# 6coils.net
KiCad netlist of a schematic drawn in EasyEDA
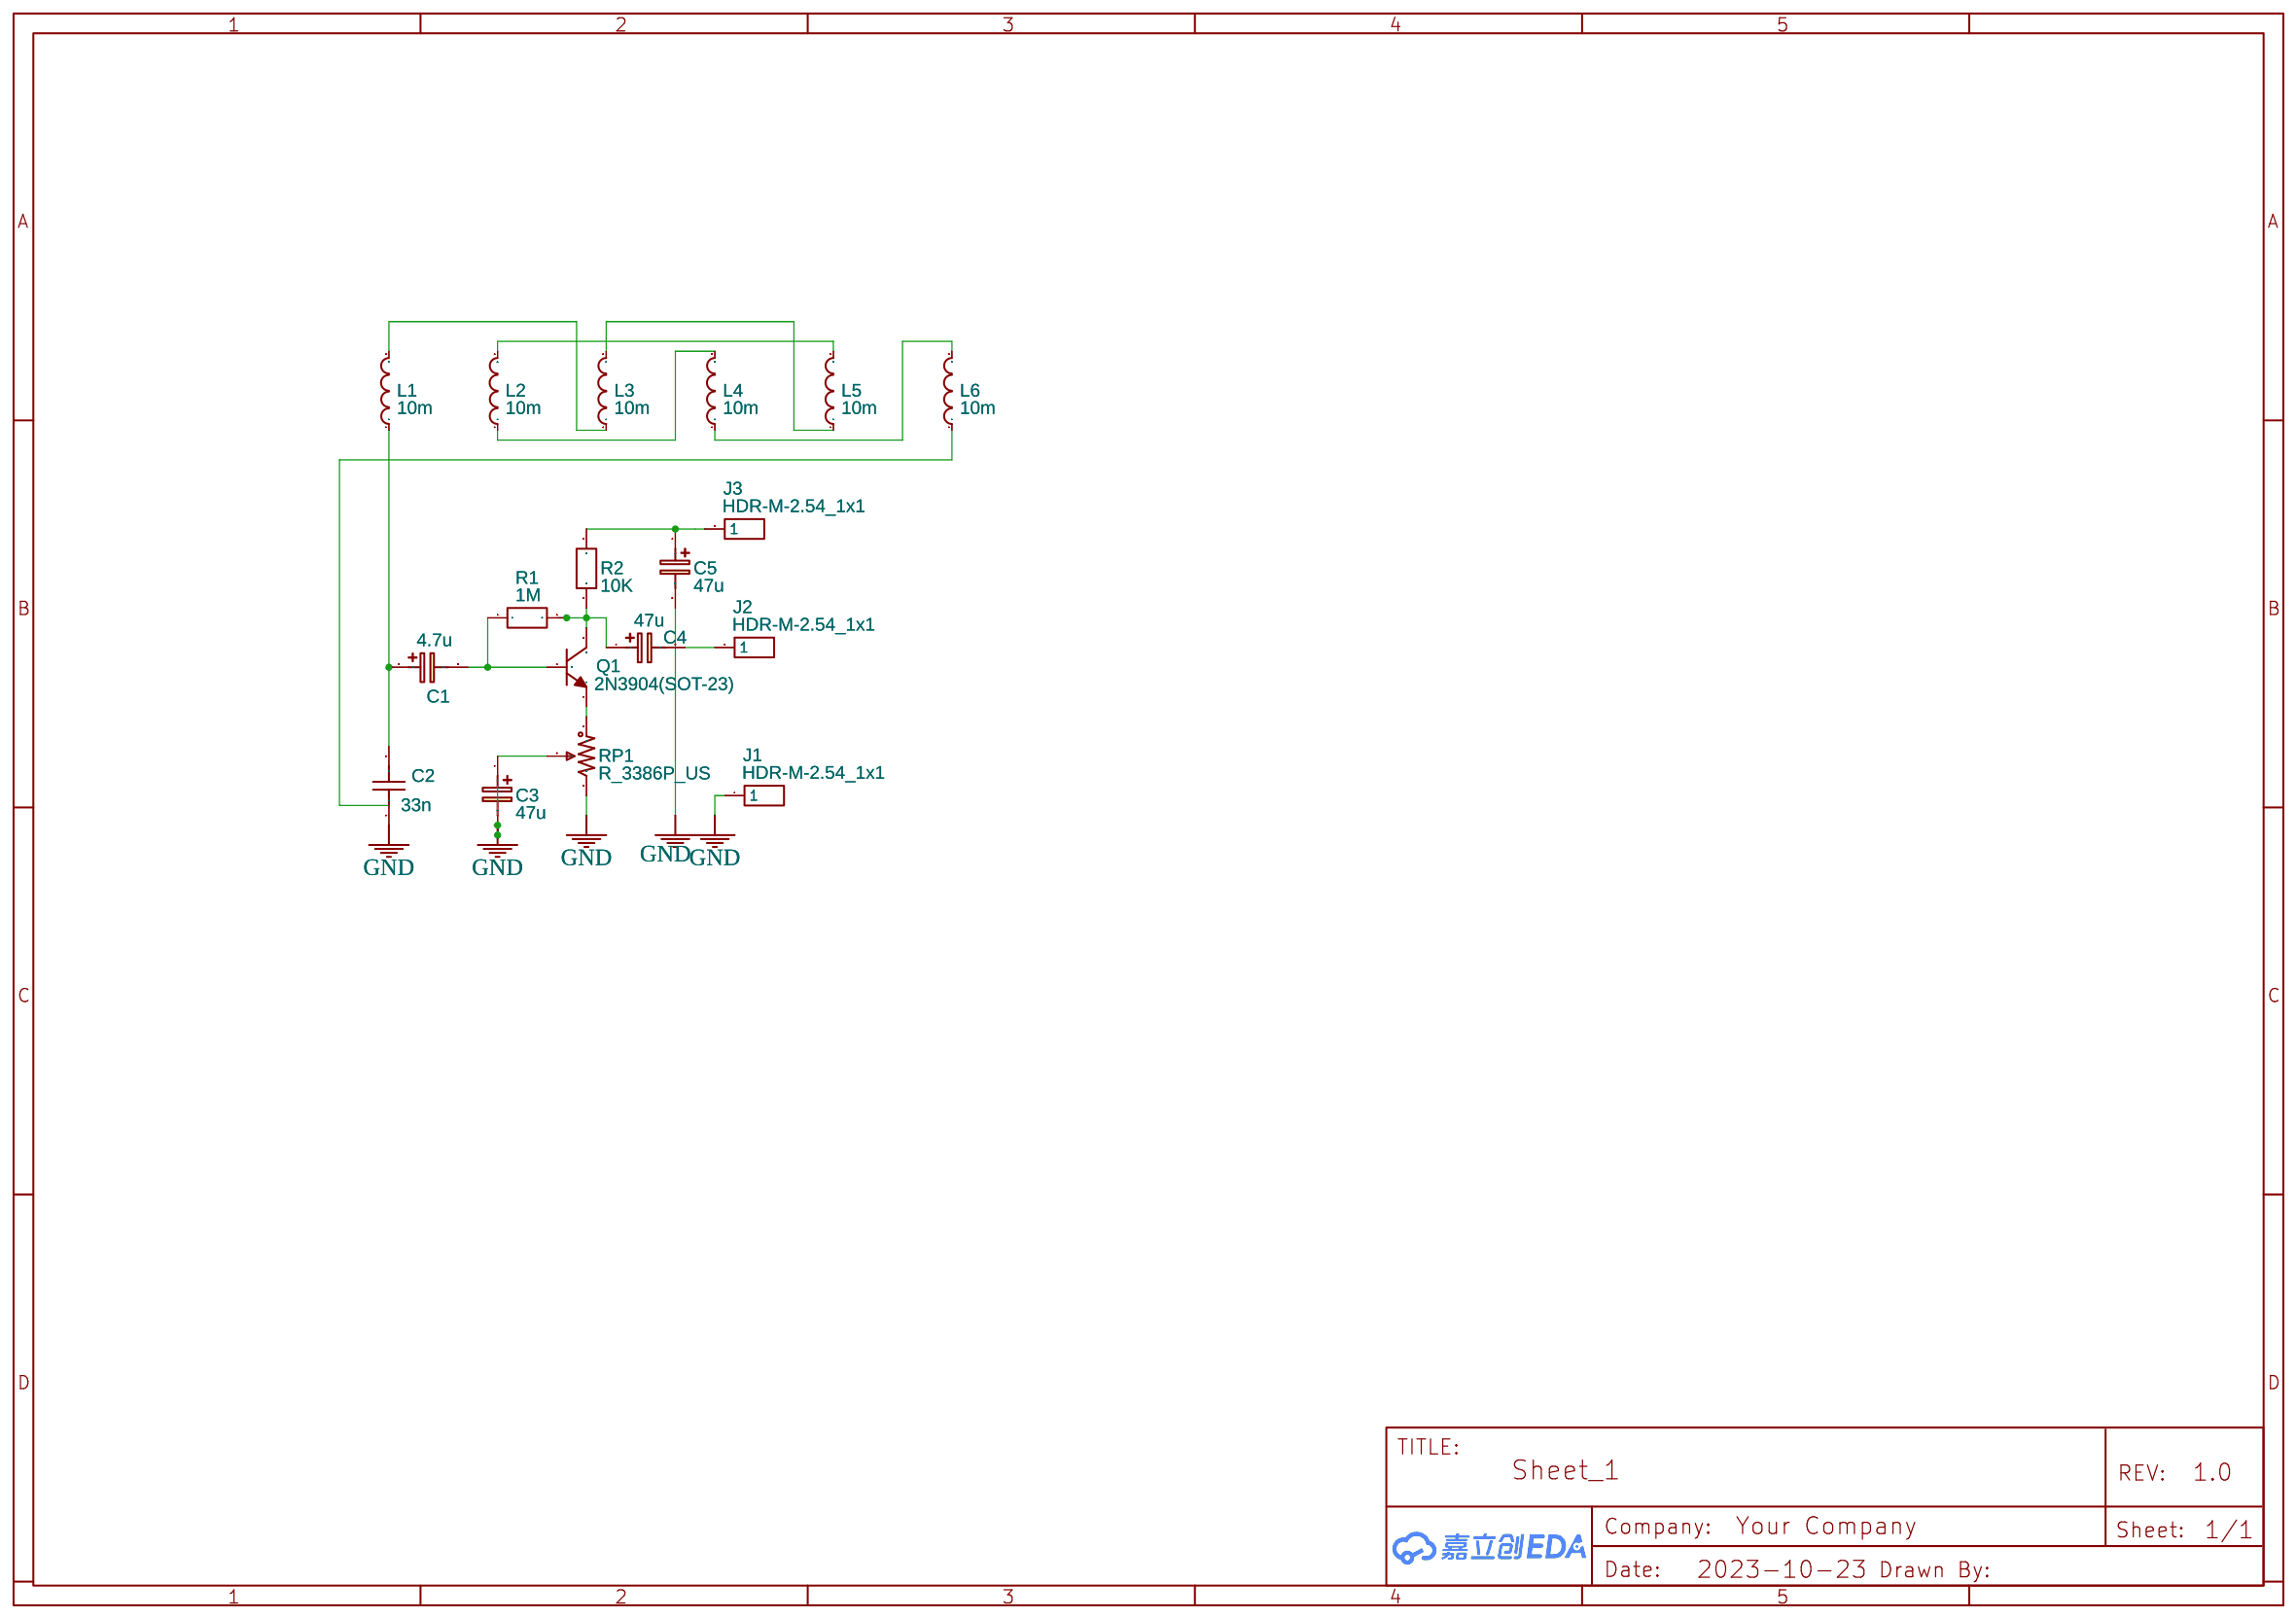
[diagram p0: schematic sheet]

(export (version "E")
  (design (tool "Eeschema 10.0.6"))
  (components
    (comp (ref "C1") (value "4.7u") (libsource (lib "") (part "C_Tan_SMD_A_EU_2")))
    (comp (ref "C2") (value "33n") (libsource (lib "") (part "C_0603_US")))
    (comp (ref "C3") (value "47u") (libsource (lib "") (part "C_Tan_SMD_A_EU")))
    (comp (ref "C4") (value "47u") (libsource (lib "") (part "C_Tan_SMD_A_EU_3")))
    (comp (ref "C5") (value "47u") (libsource (lib "") (part "C_Tan_SMD_A_EU_1")))
    (comp (ref "J1")
      (value "HDR-M-2.54_1x1")
      (fields (field (name "BOM_Supplier Part") "C81276"))
      (libsource (lib "") (part "HDR-M-2.54_1x1"))
    )
    (comp (ref "J2")
      (value "HDR-M-2.54_1x1")
      (fields (field (name "BOM_Supplier Part") "C81276"))
      (libsource (lib "") (part "HDR-M-2.54_1x1"))
    )
    (comp (ref "J3")
      (value "HDR-M-2.54_1x1")
      (fields (field (name "BOM_Supplier Part") "C81276"))
      (libsource (lib "") (part "HDR-M-2.54_1x1"))
    )
    (comp (ref "L1") (value "10m") (libsource (lib "") (part "L0603_US")))
    (comp (ref "L2") (value "10m") (libsource (lib "") (part "L0603_US")))
    (comp (ref "L3") (value "10m") (libsource (lib "") (part "L0603_US")))
    (comp (ref "L4") (value "10m") (libsource (lib "") (part "L0603_US")))
    (comp (ref "L5") (value "10m") (libsource (lib "") (part "L0603_US")))
    (comp (ref "L6") (value "10m") (libsource (lib "") (part "L0603_US")))
    (comp (ref "Q1")
      (value "2N3904(SOT-23)")
      (fields
        (field (name "BOM_Manufacturer Part") "2n3904S-RTK/PS")
        (field (name "BOM_Supplier Part") "C18536")
      )
      (libsource (lib "") (part "2N3904(SOT-23)"))
    )
    (comp (ref "R1") (value "1M") (libsource (lib "") (part "R_0603_EU_1")))
    (comp (ref "R2") (value "10K") (libsource (lib "") (part "R_0603_EU")))
    (comp (ref "RP1") (value "R_3386P_US") (libsource (lib "") (part "R_3386P_US")))
  )
  (nets
    (net (code "1") (name "GND") (class "Default")
      (node (ref "C2") (pin "1") (pinfunction "1_1") (pintype "unspecified"))
      (node (ref "C3") (pin "2") (pinfunction "2_2") (pintype "unspecified"))
      (node (ref "C5") (pin "2") (pinfunction "2_2") (pintype "unspecified"))
      (node (ref "J1") (pin "1") (pinfunction "1_1") (pintype "input"))
      (node (ref "RP1") (pin "3") (pinfunction "3_3") (pintype "unspecified"))
    )
    (net (code "2") (name "Net-(C1-Pad1)") (class "Default")
      (node (ref "C1") (pin "1") (pinfunction "1_1") (pintype "unspecified"))
      (node (ref "C2") (pin "2") (pinfunction "2_2") (pintype "unspecified"))
      (node (ref "L1") (pin "1") (pinfunction "1_1") (pintype "unspecified"))
    )
    (net (code "3") (name "Net-(C3-Pad1)") (class "Default")
      (node (ref "C3") (pin "1") (pinfunction "1_1") (pintype "unspecified"))
      (node (ref "RP1") (pin "2") (pinfunction "2_2") (pintype "unspecified"))
    )
    (net (code "4") (name "Net-(C4-Pad2)") (class "Default")
      (node (ref "C4") (pin "2") (pinfunction "2_2") (pintype "unspecified"))
      (node (ref "J2") (pin "1") (pinfunction "1_1") (pintype "input"))
    )
    (net (code "5") (name "Net-(C5-Pad1)") (class "Default")
      (node (ref "C5") (pin "1") (pinfunction "1_1") (pintype "unspecified"))
      (node (ref "J3") (pin "1") (pinfunction "1_1") (pintype "input"))
      (node (ref "R2") (pin "2") (pinfunction "2_2") (pintype "unspecified"))
    )
    (net (code "6") (name "Net-(L1-Pad2)") (class "Default")
      (node (ref "L1") (pin "2") (pinfunction "2_2") (pintype "unspecified"))
      (node (ref "L3") (pin "1") (pinfunction "1_1") (pintype "unspecified"))
    )
    (net (code "7") (name "Net-(L2-Pad1)") (class "Default")
      (node (ref "L2") (pin "1") (pinfunction "1_1") (pintype "unspecified"))
      (node (ref "L4") (pin "2") (pinfunction "2_2") (pintype "unspecified"))
    )
    (net (code "8") (name "Net-(L2-Pad2)") (class "Default")
      (node (ref "L2") (pin "2") (pinfunction "2_2") (pintype "unspecified"))
      (node (ref "L5") (pin "2") (pinfunction "2_2") (pintype "unspecified"))
    )
    (net (code "9") (name "Net-(L3-Pad2)") (class "Default")
      (node (ref "L3") (pin "2") (pinfunction "2_2") (pintype "unspecified"))
      (node (ref "L5") (pin "1") (pinfunction "1_1") (pintype "unspecified"))
    )
    (net (code "10") (name "Net-(L4-Pad1)") (class "Default")
      (node (ref "L4") (pin "1") (pinfunction "1_1") (pintype "unspecified"))
      (node (ref "L6") (pin "2") (pinfunction "2_2") (pintype "unspecified"))
    )
    (net (code "11") (name "Net-(Q1-B)") (class "Default")
      (node (ref "C1") (pin "2") (pinfunction "2_2") (pintype "unspecified"))
      (node (ref "Q1") (pin "2") (pinfunction "B_2") (pintype "input"))
      (node (ref "R1") (pin "1") (pinfunction "1_1") (pintype "unspecified"))
    )
    (net (code "12") (name "Net-(Q1-C)") (class "Default")
      (node (ref "C4") (pin "1") (pinfunction "1_1") (pintype "unspecified"))
      (node (ref "Q1") (pin "3") (pinfunction "C_3") (pintype "input"))
      (node (ref "R1") (pin "2") (pinfunction "2_2") (pintype "unspecified"))
      (node (ref "R2") (pin "1") (pinfunction "1_1") (pintype "unspecified"))
    )
    (net (code "13") (name "Net-(Q1-E)") (class "Default")
      (node (ref "Q1") (pin "1") (pinfunction "E_1") (pintype "input"))
      (node (ref "RP1") (pin "1") (pinfunction "1_1") (pintype "unspecified"))
    )
    (net (code "14") (name "unconnected-(L6-Pad1)") (class "Default")
      (node (ref "L6") (pin "1") (pinfunction "1_1") (pintype "unspecified"))
    )
  )
)
